# Wifi-MX8M.net
KiCad netlist of a schematic drawn in Altium Designer
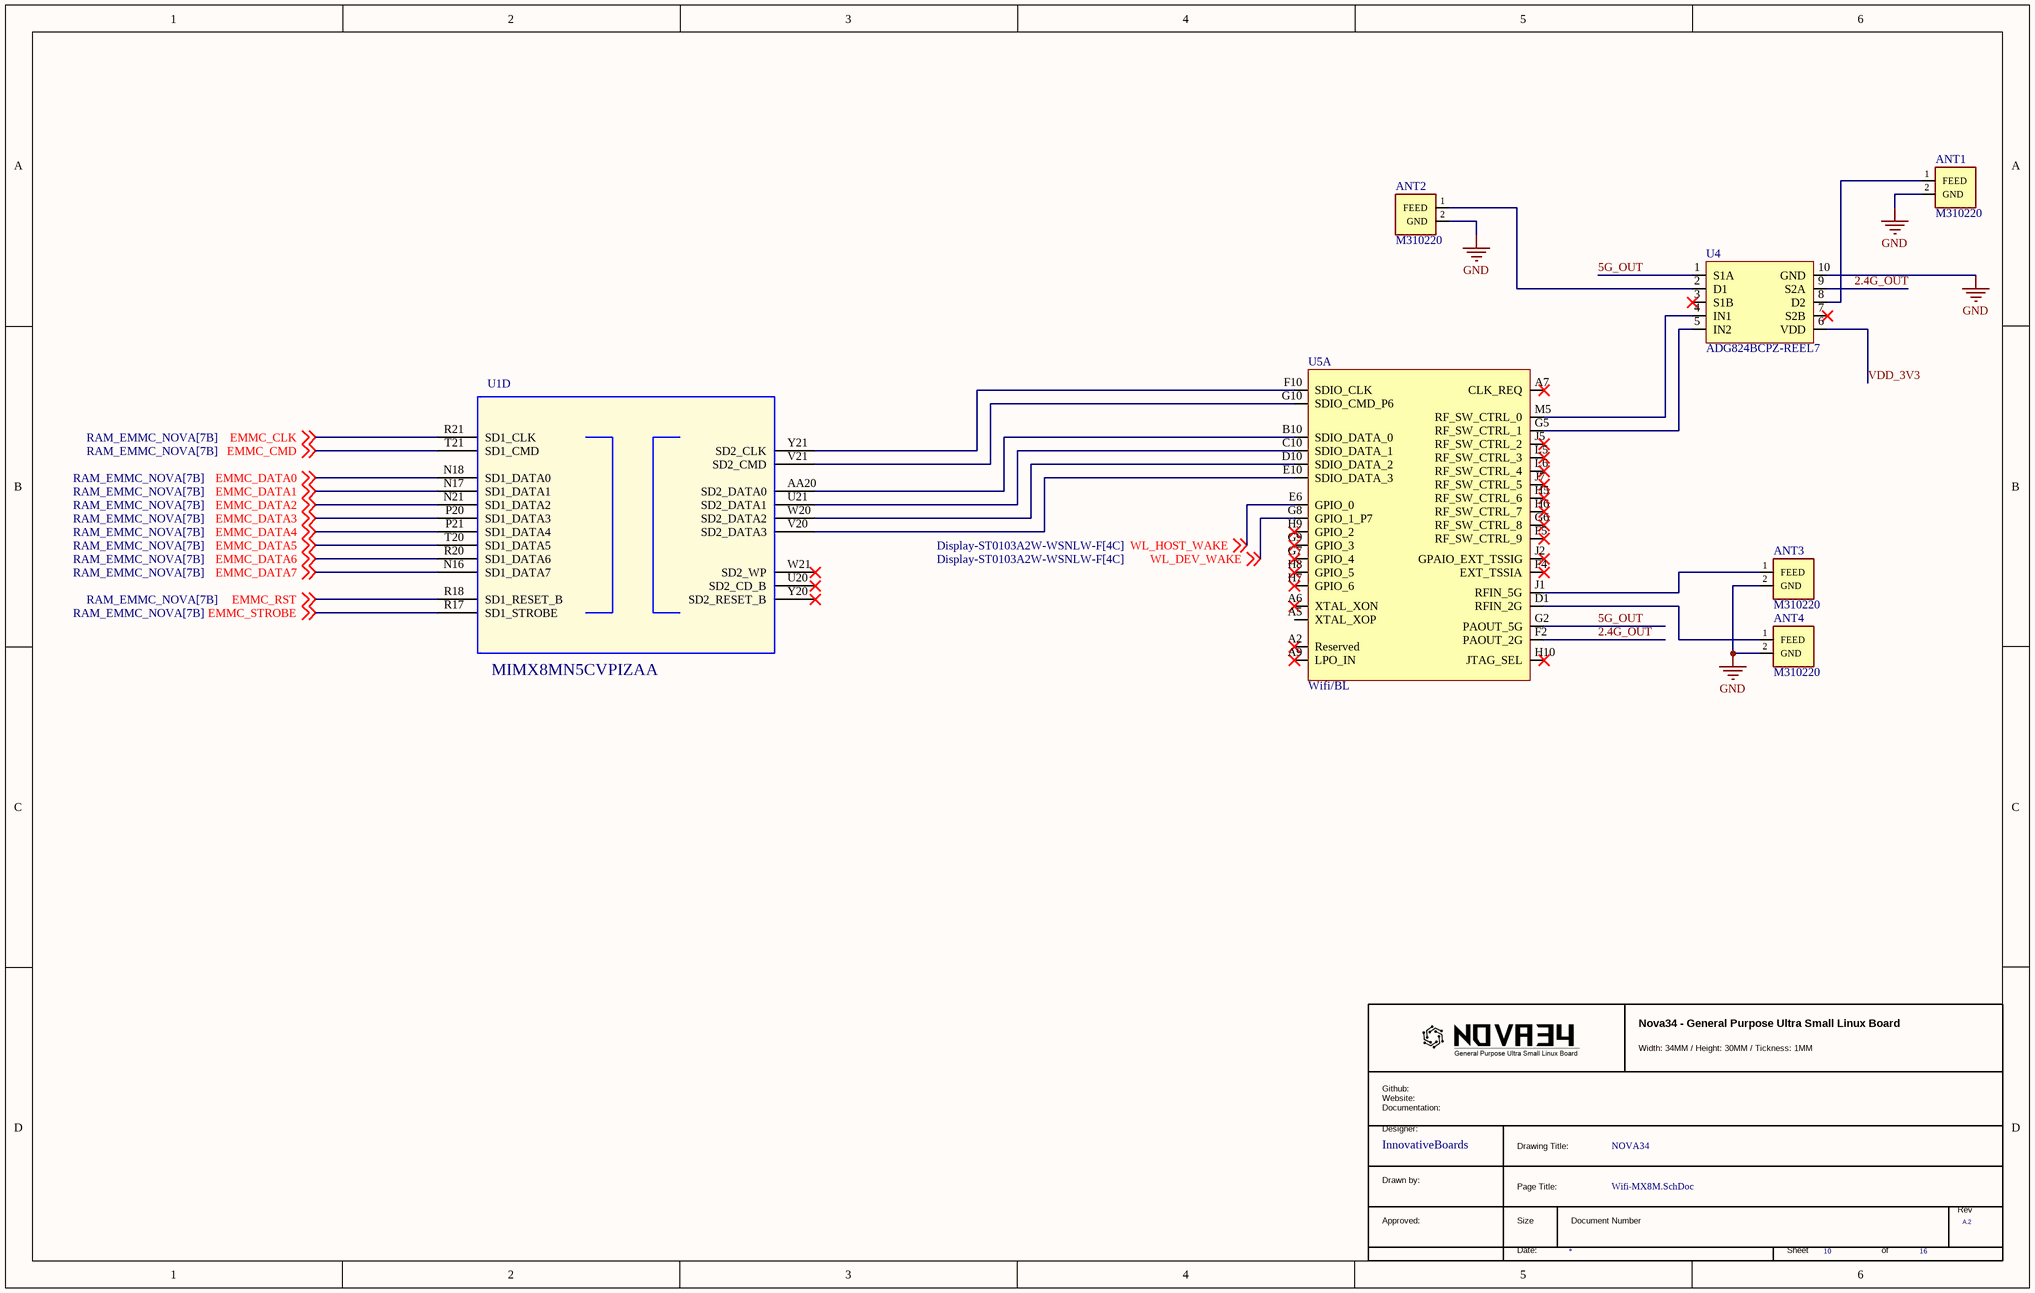
[diagram p0: Wifi-MX8M.SchDoc]

(export (version "E")
  (design (tool "Eeschema 10.0.6"))
  (components
    (comp (ref "*")
      (value "TitleBlock_MCPG")
      (fields (field (name "REVCODE") "A.2"))
      (libsource (lib "Nova_SCHLIB") (part "TitleBlock_MCPG"))
    )
    (comp (ref "ANT1")
      (value "M310220")
      (footprint "M310220")
      (description "Antennas WiFi/BT Ceramic")
      (fields (field (name "MOUSER PART NUMBER") "581-M310220"))
      (libsource (lib "") (part "M310220_1"))
    )
    (comp (ref "ANT2")
      (value "M310220")
      (footprint "M310220")
      (description "Antennas WiFi/BT Ceramic")
      (fields (field (name "MOUSER PART NUMBER") "581-M310220"))
      (libsource (lib "Nova_SCHLIB") (part "M310220"))
    )
    (comp (ref "ANT3")
      (value "M310220")
      (footprint "M310220")
      (description "Antennas WiFi/BT Ceramic")
      (fields (field (name "MOUSER PART NUMBER") "581-M310220"))
      (libsource (lib "") (part "M310220_1"))
    )
    (comp (ref "ANT4")
      (value "M310220")
      (footprint "M310220")
      (description "Antennas WiFi/BT Ceramic")
      (fields (field (name "MOUSER PART NUMBER") "581-M310220"))
      (libsource (lib "") (part "M310220_1"))
    )
    (comp (ref "U1")
      (value "MIMX8MN5CVPIZAA")
      (footprint "BGA306C50P21X21_1100X1100X101")
      (description "IC CPU QUAD CORTEX A53+M7 1.4GHZ -- BGA306")
      (libsource (lib "Nova_SCHLIB") (part "MIMX8MN"))
    )
    (comp (ref "U4")
      (value "ADG824BCPZ-REEL7")
      (footprint "ADG824")
      (description "IC SWITCH SPDTX2 800MOHM 10LFCSP")
      (libsource (lib "Nova_SCHLIB") (part "ADG824BCPZ-REEL7"))
    )
    (comp (ref "U5")
      (value "Wifi/BL")
      (footprint "106 BALL WLBGA 3.76X4.43X0.53 MM")
      (libsource (lib "Nova_SCHLIB") (part "CYW43012"))
    )
  )
  (nets
    (net (code "1") (name "/2.4G_OUT") (class "Default")
      (node (ref "U4") (pin "9") (pinfunction "S2A_9") (pintype "passive"))
      (node (ref "U5") (pin "F2") (pinfunction "PAOUT_2G_F2") (pintype "passive"))
    )
    (net (code "2") (name "/5G_OUT") (class "Default")
      (node (ref "U4") (pin "1") (pinfunction "S1A_1") (pintype "passive"))
      (node (ref "U5") (pin "G2") (pinfunction "PAOUT_5G_G2") (pintype "passive"))
    )
    (net (code "3") (name "/VDD_3V3") (class "Default")
      (node (ref "U4") (pin "6") (pinfunction "VDD_6") (pintype "passive"))
    )
    (net (code "4") (name "EMMC_CLK") (class "Default")
      (node (ref "U1") (pin "R21") (pinfunction "SD1_CLK_R21") (pintype "passive"))
    )
    (net (code "5") (name "EMMC_CMD") (class "Default")
      (node (ref "U1") (pin "T21") (pinfunction "SD1_CMD_T21") (pintype "passive"))
    )
    (net (code "6") (name "EMMC_DATA0") (class "Default")
      (node (ref "U1") (pin "N18") (pinfunction "SD1_DATA0_N18") (pintype "passive"))
    )
    (net (code "7") (name "EMMC_DATA1") (class "Default")
      (node (ref "U1") (pin "N17") (pinfunction "SD1_DATA1_N17") (pintype "passive"))
    )
    (net (code "8") (name "EMMC_DATA2") (class "Default")
      (node (ref "U1") (pin "N21") (pinfunction "SD1_DATA2_N21") (pintype "passive"))
    )
    (net (code "9") (name "EMMC_DATA3") (class "Default")
      (node (ref "U1") (pin "P20") (pinfunction "SD1_DATA3_P20") (pintype "passive"))
    )
    (net (code "10") (name "EMMC_DATA4") (class "Default")
      (node (ref "U1") (pin "P21") (pinfunction "SD1_DATA4_P21") (pintype "passive"))
    )
    (net (code "11") (name "EMMC_DATA5") (class "Default")
      (node (ref "U1") (pin "T20") (pinfunction "SD1_DATA5_T20") (pintype "passive"))
    )
    (net (code "12") (name "EMMC_DATA6") (class "Default")
      (node (ref "U1") (pin "R20") (pinfunction "SD1_DATA6_R20") (pintype "passive"))
    )
    (net (code "13") (name "EMMC_DATA7") (class "Default")
      (node (ref "U1") (pin "N16") (pinfunction "SD1_DATA7_N16") (pintype "passive"))
    )
    (net (code "14") (name "EMMC_RST") (class "Default")
      (node (ref "U1") (pin "R18") (pinfunction "SD1_RESET_B_R18") (pintype "passive"))
    )
    (net (code "15") (name "EMMC_STROBE") (class "Default")
      (node (ref "U1") (pin "R17") (pinfunction "SD1_STROBE_R17") (pintype "passive"))
    )
    (net (code "16") (name "GND") (class "Default")
      (node (ref "ANT1") (pin "2") (pinfunction "GND_2") (pintype "passive"))
      (node (ref "ANT2") (pin "2") (pinfunction "GND_2") (pintype "passive"))
      (node (ref "ANT3") (pin "2") (pinfunction "GND_2") (pintype "passive"))
      (node (ref "ANT4") (pin "2") (pinfunction "GND_2") (pintype "passive"))
      (node (ref "U4") (pin "10") (pinfunction "GND_10") (pintype "passive"))
    )
    (net (code "17") (name "Net-(ANT1-FEED)") (class "Default")
      (node (ref "ANT1") (pin "1") (pinfunction "FEED_1") (pintype "passive"))
      (node (ref "U4") (pin "8") (pinfunction "D2_8") (pintype "passive"))
    )
    (net (code "18") (name "Net-(ANT2-FEED)") (class "Default")
      (node (ref "ANT2") (pin "1") (pinfunction "FEED_1") (pintype "passive"))
      (node (ref "U4") (pin "2") (pinfunction "D1_2") (pintype "passive"))
    )
    (net (code "19") (name "Net-(ANT3-FEED)") (class "Default")
      (node (ref "ANT3") (pin "1") (pinfunction "FEED_1") (pintype "passive"))
      (node (ref "U5") (pin "J1") (pinfunction "RFIN_5G_J1") (pintype "passive"))
    )
    (net (code "20") (name "Net-(ANT4-FEED)") (class "Default")
      (node (ref "ANT4") (pin "1") (pinfunction "FEED_1") (pintype "passive"))
      (node (ref "U5") (pin "D1") (pinfunction "RFIN_2G_D1") (pintype "passive"))
    )
    (net (code "21") (name "Net-(U1D-SD2_CLK)") (class "Default")
      (node (ref "U1") (pin "Y21") (pinfunction "SD2_CLK_Y21") (pintype "passive"))
      (node (ref "U5") (pin "F10") (pinfunction "SDIO_CLK_F10") (pintype "passive"))
    )
    (net (code "22") (name "Net-(U1D-SD2_CMD)") (class "Default")
      (node (ref "U1") (pin "V21") (pinfunction "SD2_CMD_V21") (pintype "passive"))
      (node (ref "U5") (pin "G10") (pinfunction "SDIO_CMD_P6_G10") (pintype "passive"))
    )
    (net (code "23") (name "Net-(U1D-SD2_DATA0)") (class "Default")
      (node (ref "U1") (pin "AA20") (pinfunction "SD2_DATA0_AA20") (pintype "passive"))
      (node (ref "U5") (pin "B10") (pinfunction "SDIO_DATA_0_B10") (pintype "passive"))
    )
    (net (code "24") (name "Net-(U1D-SD2_DATA1)") (class "Default")
      (node (ref "U1") (pin "U21") (pinfunction "SD2_DATA1_U21") (pintype "passive"))
      (node (ref "U5") (pin "C10") (pinfunction "SDIO_DATA_1_C10") (pintype "passive"))
    )
    (net (code "25") (name "Net-(U1D-SD2_DATA2)") (class "Default")
      (node (ref "U1") (pin "W20") (pinfunction "SD2_DATA2_W20") (pintype "passive"))
      (node (ref "U5") (pin "D10") (pinfunction "SDIO_DATA_2_D10") (pintype "passive"))
    )
    (net (code "26") (name "Net-(U1D-SD2_DATA3)") (class "Default")
      (node (ref "U1") (pin "V20") (pinfunction "SD2_DATA3_V20") (pintype "passive"))
      (node (ref "U5") (pin "E10") (pinfunction "SDIO_DATA_3_E10") (pintype "passive"))
    )
    (net (code "27") (name "Net-(U4-IN1)") (class "Default")
      (node (ref "U4") (pin "4") (pinfunction "IN1_4") (pintype "passive"))
      (node (ref "U5") (pin "M5") (pinfunction "RF_SW_CTRL_0_M5") (pintype "passive"))
    )
    (net (code "28") (name "Net-(U4-IN2)") (class "Default")
      (node (ref "U4") (pin "5") (pinfunction "IN2_5") (pintype "passive"))
      (node (ref "U5") (pin "G5") (pinfunction "RF_SW_CTRL_1_G5") (pintype "passive"))
    )
    (net (code "29") (name "WL_DEV_WAKE") (class "Default")
      (node (ref "U5") (pin "G8") (pinfunction "GPIO_1_P7_G8") (pintype "passive"))
    )
    (net (code "30") (name "WL_HOST_WAKE") (class "Default")
      (node (ref "U5") (pin "E6") (pinfunction "GPIO_0_E6") (pintype "passive"))
    )
    (net (code "31") (name "unconnected-(U1D-SD2_CD_B-PadU20)") (class "Default")
      (node (ref "U1") (pin "U20") (pinfunction "SD2_CD_B_U20") (pintype "passive+no_connect"))
    )
    (net (code "32") (name "unconnected-(U1D-SD2_RESET_B-PadY20)") (class "Default")
      (node (ref "U1") (pin "Y20") (pinfunction "SD2_RESET_B_Y20") (pintype "passive+no_connect"))
    )
    (net (code "33") (name "unconnected-(U1D-SD2_WP-PadW21)") (class "Default")
      (node (ref "U1") (pin "W21") (pinfunction "SD2_WP_W21") (pintype "passive+no_connect"))
    )
    (net (code "34") (name "unconnected-(U4-S1B-Pad3)") (class "Default")
      (node (ref "U4") (pin "3") (pinfunction "S1B_3") (pintype "passive+no_connect"))
    )
    (net (code "35") (name "unconnected-(U4-S2B-Pad7)") (class "Default")
      (node (ref "U4") (pin "7") (pinfunction "S2B_7") (pintype "passive+no_connect"))
    )
    (net (code "36") (name "unconnected-(U5A-CLK_REQ-PadA7)") (class "Default")
      (node (ref "U5") (pin "A7") (pinfunction "CLK_REQ_A7") (pintype "passive+no_connect"))
    )
    (net (code "37") (name "unconnected-(U5A-EXT_TSSIA-PadF4)") (class "Default")
      (node (ref "U5") (pin "F4") (pinfunction "EXT_TSSIA_F4") (pintype "passive+no_connect"))
    )
    (net (code "38") (name "unconnected-(U5A-GPAIO_EXT_TSSIG-PadJ2)") (class "Default")
      (node (ref "U5") (pin "J2") (pinfunction "GPAIO_EXT_TSSIG_J2") (pintype "passive+no_connect"))
    )
    (net (code "39") (name "unconnected-(U5A-GPIO_2-PadH9)") (class "Default")
      (node (ref "U5") (pin "H9") (pinfunction "GPIO_2_H9") (pintype "passive+no_connect"))
    )
    (net (code "40") (name "unconnected-(U5A-GPIO_3-PadG9)") (class "Default")
      (node (ref "U5") (pin "G9") (pinfunction "GPIO_3_G9") (pintype "passive+no_connect"))
    )
    (net (code "41") (name "unconnected-(U5A-GPIO_4-PadG7)") (class "Default")
      (node (ref "U5") (pin "G7") (pinfunction "GPIO_4_G7") (pintype "passive+no_connect"))
    )
    (net (code "42") (name "unconnected-(U5A-GPIO_5-PadH8)") (class "Default")
      (node (ref "U5") (pin "H8") (pinfunction "GPIO_5_H8") (pintype "passive+no_connect"))
    )
    (net (code "43") (name "unconnected-(U5A-GPIO_6-PadH7)") (class "Default")
      (node (ref "U5") (pin "H7") (pinfunction "GPIO_6_H7") (pintype "passive+no_connect"))
    )
    (net (code "44") (name "unconnected-(U5A-JTAG_SEL-PadH10)") (class "Default")
      (node (ref "U5") (pin "H10") (pinfunction "JTAG_SEL_H10") (pintype "passive+no_connect"))
    )
    (net (code "45") (name "unconnected-(U5A-LPO_IN-PadA9)") (class "Default")
      (node (ref "U5") (pin "A9") (pinfunction "LPO_IN_A9") (pintype "passive+no_connect"))
    )
    (net (code "46") (name "unconnected-(U5A-RF_SW_CTRL_2-PadJ5)") (class "Default")
      (node (ref "U5") (pin "J5") (pinfunction "RF_SW_CTRL_2_J5") (pintype "passive+no_connect"))
    )
    (net (code "47") (name "unconnected-(U5A-RF_SW_CTRL_3-PadL5)") (class "Default")
      (node (ref "U5") (pin "L5") (pinfunction "RF_SW_CTRL_3_L5") (pintype "passive+no_connect"))
    )
    (net (code "48") (name "unconnected-(U5A-RF_SW_CTRL_4-PadL6)") (class "Default")
      (node (ref "U5") (pin "L6") (pinfunction "RF_SW_CTRL_4_L6") (pintype "passive+no_connect"))
    )
    (net (code "49") (name "unconnected-(U5A-RF_SW_CTRL_5-PadJ7)") (class "Default")
      (node (ref "U5") (pin "J7") (pinfunction "RF_SW_CTRL_5_J7") (pintype "passive+no_connect"))
    )
    (net (code "50") (name "unconnected-(U5A-RF_SW_CTRL_6-PadH5)") (class "Default")
      (node (ref "U5") (pin "H5") (pinfunction "RF_SW_CTRL_6_H5") (pintype "passive+no_connect"))
    )
    (net (code "51") (name "unconnected-(U5A-RF_SW_CTRL_7-PadH6)") (class "Default")
      (node (ref "U5") (pin "H6") (pinfunction "RF_SW_CTRL_7_H6") (pintype "passive+no_connect"))
    )
    (net (code "52") (name "unconnected-(U5A-RF_SW_CTRL_8-PadG6)") (class "Default")
      (node (ref "U5") (pin "G6") (pinfunction "RF_SW_CTRL_8_G6") (pintype "passive+no_connect"))
    )
    (net (code "53") (name "unconnected-(U5A-RF_SW_CTRL_9-PadF5)") (class "Default")
      (node (ref "U5") (pin "F5") (pinfunction "RF_SW_CTRL_9_F5") (pintype "passive+no_connect"))
    )
    (net (code "54") (name "unconnected-(U5A-Reserved-PadA2)") (class "Default")
      (node (ref "U5") (pin "A2") (pinfunction "Reserved_A2") (pintype "passive+no_connect"))
    )
    (net (code "55") (name "unconnected-(U5A-XTAL_XON-PadA6)") (class "Default")
      (node (ref "U5") (pin "A6") (pinfunction "XTAL_XON_A6") (pintype "passive+no_connect"))
    )
    (net (code "56") (name "unconnected-(U5A-XTAL_XOP-PadA5)") (class "Default")
      (node (ref "U5") (pin "A5") (pinfunction "XTAL_XOP_A5") (pintype "passive"))
    )
  )
)
